# SolarPwrOption_ssr.net
KiCad netlist of a schematic drawn in EAGLE
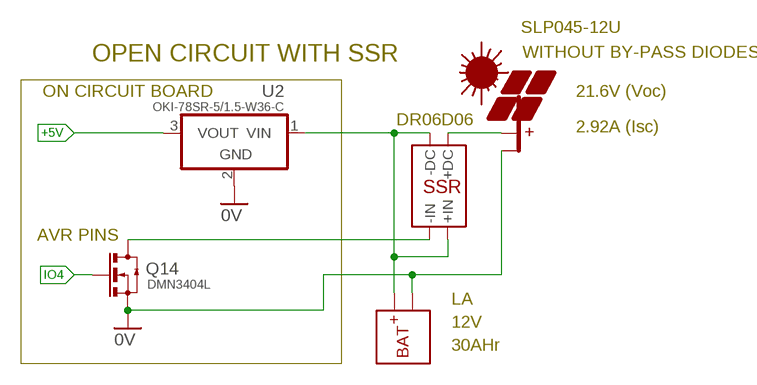
[diagram p0: schematic, sheet 1]

(export (version "E")
  (design (tool "Eeschema 10.0.6"))
  (components
    (comp (ref "PV3")
      (value "PV")
      (footprint "eagle-import:NA-30")
      (libsource (lib "eagle-import") (part "PV"))
    )
    (comp (ref "Q14")
      (value "DMN3404L")
      (footprint "eagle-import:DPAK")
      (libsource (lib "eagle-import") (part "N-CH?DPAK"))
    )
    (comp (ref "U$2")
      (value "BAT")
      (footprint "eagle-import:NA-30")
      (libsource (lib "eagle-import") (part "BAT"))
    )
    (comp (ref "U$3")
      (value "SSR_DC")
      (footprint "eagle-import:NA-30")
      (libsource (lib "eagle-import") (part "SSR_DC"))
    )
    (comp (ref "U2")
      (value "OKI-78SR-5/1.5-W36-C")
      (footprint "eagle-import:OKI-78SR-H")
      (libsource (lib "eagle-import") (part "OKI-78SR-H"))
    )
  )
  (nets
    (net (code "1") (name "+5V") (class "Default")
      (node (ref "U2") (pin "3") (pinfunction "VOUT_3") (pintype "passive"))
    )
    (net (code "2") (name "0V") (class "Default")
      (node (ref "PV3") (pin "2") (pinfunction "-PV_2") (pintype "bidirectional"))
      (node (ref "Q14") (pin "3") (pinfunction "S_3") (pintype "passive"))
      (node (ref "U$2") (pin "2") (pinfunction "-BAT_2") (pintype "bidirectional"))
      (node (ref "U2") (pin "2") (pinfunction "GND_2") (pintype "passive"))
    )
    (net (code "3") (name "IO4") (class "Default")
      (node (ref "Q14") (pin "1") (pinfunction "G_1") (pintype "passive"))
    )
    (net (code "4") (name "Net-(PV3-+PV)") (class "Default")
      (node (ref "PV3") (pin "1") (pinfunction "+PV_1") (pintype "bidirectional"))
      (node (ref "U$3") (pin "1") (pinfunction "+DC_1") (pintype "bidirectional"))
    )
    (net (code "5") (name "Net-(Q14-D)") (class "Default")
      (node (ref "Q14") (pin "SINK") (pinfunction "D_SINK") (pintype "passive"))
      (node (ref "U$3") (pin "4") (pinfunction "-IN_4") (pintype "bidirectional"))
    )
    (net (code "6") (name "Net-(U$2-+BAT)") (class "Default")
      (node (ref "U$2") (pin "1") (pinfunction "+BAT_1") (pintype "bidirectional"))
      (node (ref "U$3") (pin "2") (pinfunction "+IN_2") (pintype "bidirectional"))
      (node (ref "U$3") (pin "3") (pinfunction "-DC_3") (pintype "bidirectional"))
      (node (ref "U2") (pin "1") (pinfunction "VIN_1") (pintype "passive"))
    )
  )
)
